# Sensor_tile.net
KiCad netlist of a schematic drawn in EAGLE
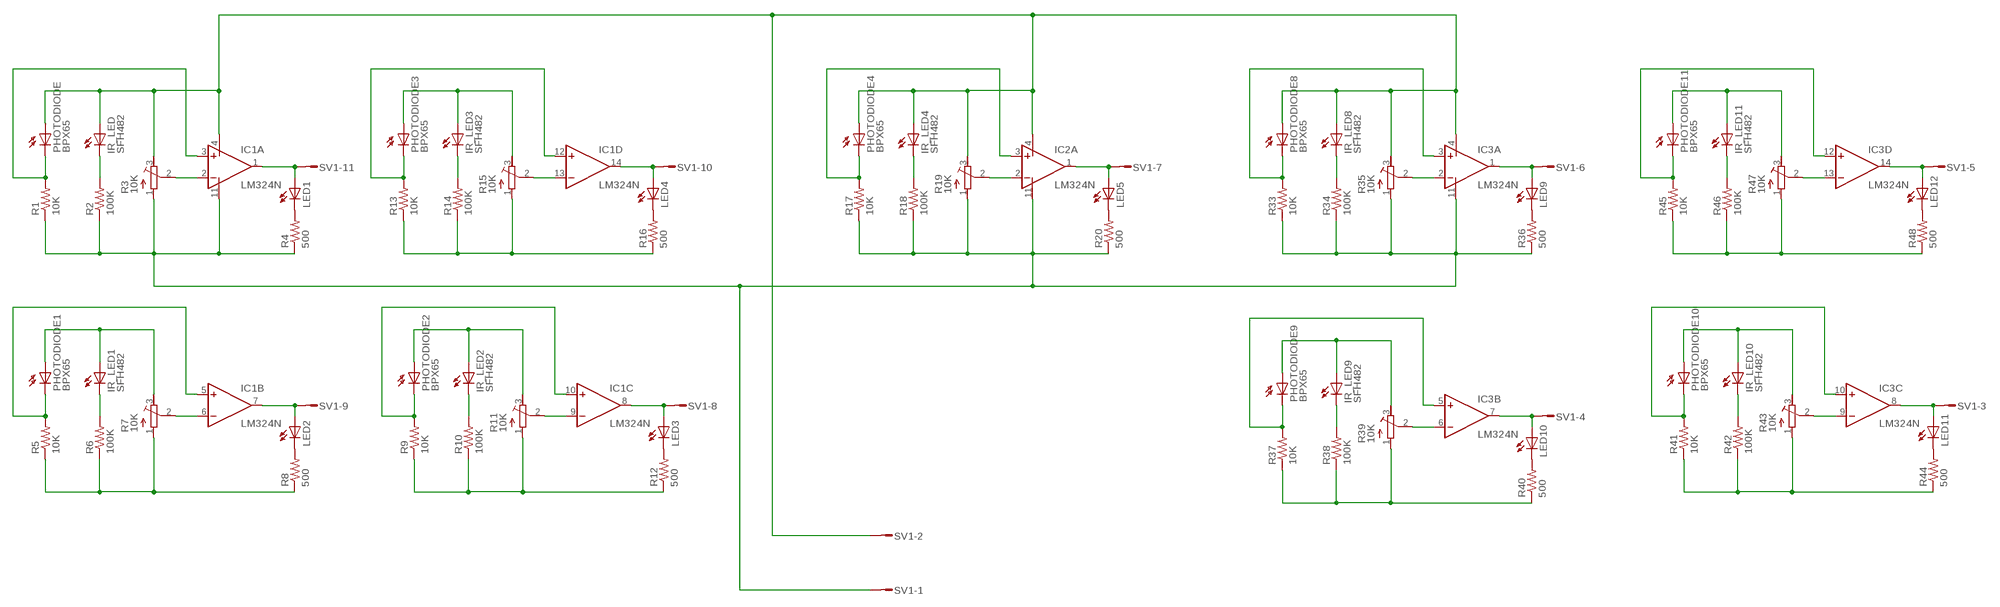
[diagram p0: schematic, sheet 1]

(export (version "E")
  (design (tool "Eeschema 10.0.6"))
  (components
    (comp (ref "IC1")
      (value "LM324N")
      (footprint "eagle-import:DIL14")
      (libsource (lib "eagle-import") (part "LM324N"))
    )
    (comp (ref "IC2")
      (value "LM324N")
      (footprint "eagle-import:DIL14")
      (libsource (lib "eagle-import") (part "LM324N"))
    )
    (comp (ref "IC3")
      (value "LM324N")
      (footprint "eagle-import:DIL14")
      (libsource (lib "eagle-import") (part "LM324N"))
    )
    (comp (ref "IR_LED")
      (value "SFH482")
      (footprint "eagle-import:SFH482")
      (libsource (lib "eagle-import") (part "SFH482"))
    )
    (comp (ref "IR_LED1")
      (value "SFH482")
      (footprint "eagle-import:SFH482")
      (libsource (lib "eagle-import") (part "SFH482"))
    )
    (comp (ref "IR_LED2")
      (value "SFH482")
      (footprint "eagle-import:SFH482")
      (libsource (lib "eagle-import") (part "SFH482"))
    )
    (comp (ref "IR_LED3")
      (value "SFH482")
      (footprint "eagle-import:SFH482")
      (libsource (lib "eagle-import") (part "SFH482"))
    )
    (comp (ref "IR_LED4")
      (value "SFH482")
      (footprint "eagle-import:SFH482")
      (libsource (lib "eagle-import") (part "SFH482"))
    )
    (comp (ref "IR_LED8")
      (value "SFH482")
      (footprint "eagle-import:SFH482")
      (libsource (lib "eagle-import") (part "SFH482"))
    )
    (comp (ref "IR_LED9")
      (value "SFH482")
      (footprint "eagle-import:SFH482")
      (libsource (lib "eagle-import") (part "SFH482"))
    )
    (comp (ref "IR_LED10")
      (value "SFH482")
      (footprint "eagle-import:SFH482")
      (libsource (lib "eagle-import") (part "SFH482"))
    )
    (comp (ref "IR_LED11")
      (value "SFH482")
      (footprint "eagle-import:SFH482")
      (libsource (lib "eagle-import") (part "SFH482"))
    )
    (comp (ref "LED1")
      (value "LED5MM")
      (footprint "eagle-import:LED5MM")
      (libsource (lib "eagle-import") (part "LED5MM"))
    )
    (comp (ref "LED2")
      (value "LED5MM")
      (footprint "eagle-import:LED5MM")
      (libsource (lib "eagle-import") (part "LED5MM"))
    )
    (comp (ref "LED3")
      (value "LED5MM")
      (footprint "eagle-import:LED5MM")
      (libsource (lib "eagle-import") (part "LED5MM"))
    )
    (comp (ref "LED4")
      (value "LED5MM")
      (footprint "eagle-import:LED5MM")
      (libsource (lib "eagle-import") (part "LED5MM"))
    )
    (comp (ref "LED5")
      (value "LED5MM")
      (footprint "eagle-import:LED5MM")
      (libsource (lib "eagle-import") (part "LED5MM"))
    )
    (comp (ref "LED9")
      (value "LED5MM")
      (footprint "eagle-import:LED5MM")
      (libsource (lib "eagle-import") (part "LED5MM"))
    )
    (comp (ref "LED10")
      (value "LED5MM")
      (footprint "eagle-import:LED5MM")
      (libsource (lib "eagle-import") (part "LED5MM"))
    )
    (comp (ref "LED11")
      (value "LED5MM")
      (footprint "eagle-import:LED5MM")
      (libsource (lib "eagle-import") (part "LED5MM"))
    )
    (comp (ref "LED12")
      (value "LED5MM")
      (footprint "eagle-import:LED5MM")
      (libsource (lib "eagle-import") (part "LED5MM"))
    )
    (comp (ref "PHOTODIODE")
      (value "BPX65")
      (footprint "eagle-import:BPX65")
      (fields (field (name "MPN") "BPX65."))
      (libsource (lib "eagle-import") (part "BPX65"))
    )
    (comp (ref "PHOTODIODE1")
      (value "BPX65")
      (footprint "eagle-import:BPX65")
      (fields (field (name "MPN") "BPX65."))
      (libsource (lib "eagle-import") (part "BPX65"))
    )
    (comp (ref "PHOTODIODE2")
      (value "BPX65")
      (footprint "eagle-import:BPX65")
      (fields (field (name "MPN") "BPX65."))
      (libsource (lib "eagle-import") (part "BPX65"))
    )
    (comp (ref "PHOTODIODE3")
      (value "BPX65")
      (footprint "eagle-import:BPX65")
      (fields (field (name "MPN") "BPX65."))
      (libsource (lib "eagle-import") (part "BPX65"))
    )
    (comp (ref "PHOTODIODE4")
      (value "BPX65")
      (footprint "eagle-import:BPX65")
      (fields (field (name "MPN") "BPX65."))
      (libsource (lib "eagle-import") (part "BPX65"))
    )
    (comp (ref "PHOTODIODE8")
      (value "BPX65")
      (footprint "eagle-import:BPX65")
      (fields (field (name "MPN") "BPX65."))
      (libsource (lib "eagle-import") (part "BPX65"))
    )
    (comp (ref "PHOTODIODE9")
      (value "BPX65")
      (footprint "eagle-import:BPX65")
      (fields (field (name "MPN") "BPX65."))
      (libsource (lib "eagle-import") (part "BPX65"))
    )
    (comp (ref "PHOTODIODE10")
      (value "BPX65")
      (footprint "eagle-import:BPX65")
      (fields (field (name "MPN") "BPX65."))
      (libsource (lib "eagle-import") (part "BPX65"))
    )
    (comp (ref "PHOTODIODE11")
      (value "BPX65")
      (footprint "eagle-import:BPX65")
      (fields (field (name "MPN") "BPX65."))
      (libsource (lib "eagle-import") (part "BPX65"))
    )
    (comp (ref "R1")
      (value "10K")
      (footprint "eagle-import:0204_7")
      (libsource (lib "eagle-import") (part "R-US_0204/7"))
    )
    (comp (ref "R2")
      (value "100K")
      (footprint "eagle-import:0204_7")
      (libsource (lib "eagle-import") (part "R-US_0204/7"))
    )
    (comp (ref "R3")
      (value "10K")
      (footprint "eagle-import:RTRIM4G_J")
      (libsource (lib "eagle-import") (part "R-TRIMM4G/J"))
    )
    (comp (ref "R4")
      (value "500")
      (footprint "eagle-import:0204_7")
      (libsource (lib "eagle-import") (part "R-US_0204/7"))
    )
    (comp (ref "R5")
      (value "10K")
      (footprint "eagle-import:0204_7")
      (libsource (lib "eagle-import") (part "R-US_0204/7"))
    )
    (comp (ref "R6")
      (value "100K")
      (footprint "eagle-import:0204_7")
      (libsource (lib "eagle-import") (part "R-US_0204/7"))
    )
    (comp (ref "R7")
      (value "10K")
      (footprint "eagle-import:RTRIM4G_J")
      (libsource (lib "eagle-import") (part "R-TRIMM4G/J"))
    )
    (comp (ref "R8")
      (value "500")
      (footprint "eagle-import:0204_7")
      (libsource (lib "eagle-import") (part "R-US_0204/7"))
    )
    (comp (ref "R9")
      (value "10K")
      (footprint "eagle-import:0204_7")
      (libsource (lib "eagle-import") (part "R-US_0204/7"))
    )
    (comp (ref "R10")
      (value "100K")
      (footprint "eagle-import:0204_7")
      (libsource (lib "eagle-import") (part "R-US_0204/7"))
    )
    (comp (ref "R11")
      (value "10K")
      (footprint "eagle-import:RTRIM4G_J")
      (libsource (lib "eagle-import") (part "R-TRIMM4G/J"))
    )
    (comp (ref "R12")
      (value "500")
      (footprint "eagle-import:0204_7")
      (libsource (lib "eagle-import") (part "R-US_0204/7"))
    )
    (comp (ref "R13")
      (value "10K")
      (footprint "eagle-import:0204_7")
      (libsource (lib "eagle-import") (part "R-US_0204/7"))
    )
    (comp (ref "R14")
      (value "100K")
      (footprint "eagle-import:0204_7")
      (libsource (lib "eagle-import") (part "R-US_0204/7"))
    )
    (comp (ref "R15")
      (value "10K")
      (footprint "eagle-import:RTRIM4G_J")
      (libsource (lib "eagle-import") (part "R-TRIMM4G/J"))
    )
    (comp (ref "R16")
      (value "500")
      (footprint "eagle-import:0204_7")
      (libsource (lib "eagle-import") (part "R-US_0204/7"))
    )
    (comp (ref "R17")
      (value "10K")
      (footprint "eagle-import:0204_7")
      (libsource (lib "eagle-import") (part "R-US_0204/7"))
    )
    (comp (ref "R18")
      (value "100K")
      (footprint "eagle-import:0204_7")
      (libsource (lib "eagle-import") (part "R-US_0204/7"))
    )
    (comp (ref "R19")
      (value "10K")
      (footprint "eagle-import:RTRIM4G_J")
      (libsource (lib "eagle-import") (part "R-TRIMM4G/J"))
    )
    (comp (ref "R20")
      (value "500")
      (footprint "eagle-import:0204_7")
      (libsource (lib "eagle-import") (part "R-US_0204/7"))
    )
    (comp (ref "R33")
      (value "10K")
      (footprint "eagle-import:0204_7")
      (libsource (lib "eagle-import") (part "R-US_0204/7"))
    )
    (comp (ref "R34")
      (value "100K")
      (footprint "eagle-import:0204_7")
      (libsource (lib "eagle-import") (part "R-US_0204/7"))
    )
    (comp (ref "R35")
      (value "10K")
      (footprint "eagle-import:RTRIM4G_J")
      (libsource (lib "eagle-import") (part "R-TRIMM4G/J"))
    )
    (comp (ref "R36")
      (value "500")
      (footprint "eagle-import:0204_7")
      (libsource (lib "eagle-import") (part "R-US_0204/7"))
    )
    (comp (ref "R37")
      (value "10K")
      (footprint "eagle-import:0204_7")
      (libsource (lib "eagle-import") (part "R-US_0204/7"))
    )
    (comp (ref "R38")
      (value "100K")
      (footprint "eagle-import:0204_7")
      (libsource (lib "eagle-import") (part "R-US_0204/7"))
    )
    (comp (ref "R39")
      (value "10K")
      (footprint "eagle-import:RTRIM4G_J")
      (libsource (lib "eagle-import") (part "R-TRIMM4G/J"))
    )
    (comp (ref "R40")
      (value "500")
      (footprint "eagle-import:0204_7")
      (libsource (lib "eagle-import") (part "R-US_0204/7"))
    )
    (comp (ref "R41")
      (value "10K")
      (footprint "eagle-import:0204_7")
      (libsource (lib "eagle-import") (part "R-US_0204/7"))
    )
    (comp (ref "R42")
      (value "100K")
      (footprint "eagle-import:0204_7")
      (libsource (lib "eagle-import") (part "R-US_0204/7"))
    )
    (comp (ref "R43")
      (value "10K")
      (footprint "eagle-import:RTRIM4G_J")
      (libsource (lib "eagle-import") (part "R-TRIMM4G/J"))
    )
    (comp (ref "R44")
      (value "500")
      (footprint "eagle-import:0204_7")
      (libsource (lib "eagle-import") (part "R-US_0204/7"))
    )
    (comp (ref "R45")
      (value "10K")
      (footprint "eagle-import:0204_7")
      (libsource (lib "eagle-import") (part "R-US_0204/7"))
    )
    (comp (ref "R46")
      (value "100K")
      (footprint "eagle-import:0204_7")
      (libsource (lib "eagle-import") (part "R-US_0204/7"))
    )
    (comp (ref "R47")
      (value "10K")
      (footprint "eagle-import:RTRIM4G_J")
      (libsource (lib "eagle-import") (part "R-TRIMM4G/J"))
    )
    (comp (ref "R48")
      (value "500")
      (footprint "eagle-import:0204_7")
      (libsource (lib "eagle-import") (part "R-US_0204/7"))
    )
    (comp (ref "SV1")
      (value "L11P")
      (footprint "eagle-import:L11P")
      (libsource (lib "eagle-import") (part "L11P"))
    )
  )
  (nets
    (net (code "1") (name "Net-(IC1A-+IN)") (class "Default")
      (node (ref "IC1") (pin "3") (pinfunction "+IN_3") (pintype "input"))
      (node (ref "PHOTODIODE") (pin "K") (pinfunction "C_K") (pintype "passive"))
      (node (ref "R1") (pin "2") (pinfunction "2_2") (pintype "passive"))
    )
    (net (code "2") (name "Net-(IC1A--IN)") (class "Default")
      (node (ref "IC1") (pin "2") (pinfunction "-IN_2") (pintype "input"))
      (node (ref "R3") (pin "2") (pinfunction "S_2") (pintype "passive"))
    )
    (net (code "3") (name "Net-(IC1A-OUT)") (class "Default")
      (node (ref "IC1") (pin "1") (pinfunction "OUT_1") (pintype "output"))
      (node (ref "LED1") (pin "A") (pinfunction "A_A") (pintype "passive"))
      (node (ref "SV1") (pin "11") (pinfunction "S_11") (pintype "passive"))
    )
    (net (code "4") (name "Net-(IC1B-+IN)") (class "Default")
      (node (ref "IC1") (pin "5") (pinfunction "+IN_5") (pintype "input"))
      (node (ref "PHOTODIODE1") (pin "K") (pinfunction "C_K") (pintype "passive"))
      (node (ref "R5") (pin "2") (pinfunction "2_2") (pintype "passive"))
    )
    (net (code "5") (name "Net-(IC1B--IN)") (class "Default")
      (node (ref "IC1") (pin "6") (pinfunction "-IN_6") (pintype "input"))
      (node (ref "R7") (pin "2") (pinfunction "S_2") (pintype "passive"))
    )
    (net (code "6") (name "Net-(IC1B-OUT)") (class "Default")
      (node (ref "IC1") (pin "7") (pinfunction "OUT_7") (pintype "output"))
      (node (ref "LED2") (pin "A") (pinfunction "A_A") (pintype "passive"))
      (node (ref "SV1") (pin "9") (pinfunction "S_9") (pintype "passive"))
    )
    (net (code "7") (name "Net-(IC1C-+IN)") (class "Default")
      (node (ref "IC1") (pin "10") (pinfunction "+IN_10") (pintype "input"))
      (node (ref "PHOTODIODE2") (pin "K") (pinfunction "C_K") (pintype "passive"))
      (node (ref "R9") (pin "2") (pinfunction "2_2") (pintype "passive"))
    )
    (net (code "8") (name "Net-(IC1C--IN)") (class "Default")
      (node (ref "IC1") (pin "9") (pinfunction "-IN_9") (pintype "input"))
      (node (ref "R11") (pin "2") (pinfunction "S_2") (pintype "passive"))
    )
    (net (code "9") (name "Net-(IC1C-OUT)") (class "Default")
      (node (ref "IC1") (pin "8") (pinfunction "OUT_8") (pintype "output"))
      (node (ref "LED3") (pin "A") (pinfunction "A_A") (pintype "passive"))
      (node (ref "SV1") (pin "8") (pinfunction "S_8") (pintype "passive"))
    )
    (net (code "10") (name "Net-(IC1D-+IN)") (class "Default")
      (node (ref "IC1") (pin "12") (pinfunction "+IN_12") (pintype "input"))
      (node (ref "PHOTODIODE3") (pin "K") (pinfunction "C_K") (pintype "passive"))
      (node (ref "R13") (pin "2") (pinfunction "2_2") (pintype "passive"))
    )
    (net (code "11") (name "Net-(IC1D--IN)") (class "Default")
      (node (ref "IC1") (pin "13") (pinfunction "-IN_13") (pintype "input"))
      (node (ref "R15") (pin "2") (pinfunction "S_2") (pintype "passive"))
    )
    (net (code "12") (name "Net-(IC1D-OUT)") (class "Default")
      (node (ref "IC1") (pin "14") (pinfunction "OUT_14") (pintype "output"))
      (node (ref "LED4") (pin "A") (pinfunction "A_A") (pintype "passive"))
      (node (ref "SV1") (pin "10") (pinfunction "S_10") (pintype "passive"))
    )
    (net (code "13") (name "Net-(IC1E-V+)") (class "Default")
      (node (ref "IC1") (pin "4") (pinfunction "V+_4") (pintype "power_in"))
      (node (ref "IC2") (pin "4") (pinfunction "V+_4") (pintype "power_in"))
      (node (ref "IC3") (pin "4") (pinfunction "V+_4") (pintype "power_in"))
      (node (ref "IR_LED") (pin "A") (pinfunction "A_A") (pintype "passive"))
      (node (ref "IR_LED4") (pin "A") (pinfunction "A_A") (pintype "passive"))
      (node (ref "IR_LED8") (pin "A") (pinfunction "A_A") (pintype "passive"))
      (node (ref "PHOTODIODE") (pin "A") (pinfunction "A_A") (pintype "passive"))
      (node (ref "PHOTODIODE4") (pin "A") (pinfunction "A_A") (pintype "passive"))
      (node (ref "PHOTODIODE8") (pin "A") (pinfunction "A_A") (pintype "passive"))
      (node (ref "R19") (pin "3") (pinfunction "E_3") (pintype "passive"))
      (node (ref "R3") (pin "3") (pinfunction "E_3") (pintype "passive"))
      (node (ref "R35") (pin "3") (pinfunction "E_3") (pintype "passive"))
      (node (ref "SV1") (pin "2") (pinfunction "S_2") (pintype "passive"))
    )
    (net (code "14") (name "Net-(IC1E-V-)") (class "Default")
      (node (ref "IC1") (pin "11") (pinfunction "V-_11") (pintype "power_in"))
      (node (ref "IC2") (pin "11") (pinfunction "V-_11") (pintype "power_in"))
      (node (ref "IC3") (pin "11") (pinfunction "V-_11") (pintype "power_in"))
      (node (ref "R1") (pin "1") (pinfunction "1_1") (pintype "passive"))
      (node (ref "R17") (pin "1") (pinfunction "1_1") (pintype "passive"))
      (node (ref "R18") (pin "1") (pinfunction "1_1") (pintype "passive"))
      (node (ref "R19") (pin "1") (pinfunction "A_1") (pintype "passive"))
      (node (ref "R2") (pin "1") (pinfunction "1_1") (pintype "passive"))
      (node (ref "R20") (pin "1") (pinfunction "1_1") (pintype "passive"))
      (node (ref "R3") (pin "1") (pinfunction "A_1") (pintype "passive"))
      (node (ref "R33") (pin "1") (pinfunction "1_1") (pintype "passive"))
      (node (ref "R34") (pin "1") (pinfunction "1_1") (pintype "passive"))
      (node (ref "R35") (pin "1") (pinfunction "A_1") (pintype "passive"))
      (node (ref "R36") (pin "1") (pinfunction "1_1") (pintype "passive"))
      (node (ref "R4") (pin "1") (pinfunction "1_1") (pintype "passive"))
      (node (ref "SV1") (pin "1") (pinfunction "S_1") (pintype "passive"))
    )
    (net (code "15") (name "Net-(IC2A-+IN)") (class "Default")
      (node (ref "IC2") (pin "3") (pinfunction "+IN_3") (pintype "input"))
      (node (ref "PHOTODIODE4") (pin "K") (pinfunction "C_K") (pintype "passive"))
      (node (ref "R17") (pin "2") (pinfunction "2_2") (pintype "passive"))
    )
    (net (code "16") (name "Net-(IC2A--IN)") (class "Default")
      (node (ref "IC2") (pin "2") (pinfunction "-IN_2") (pintype "input"))
      (node (ref "R19") (pin "2") (pinfunction "S_2") (pintype "passive"))
    )
    (net (code "17") (name "Net-(IC2A-OUT)") (class "Default")
      (node (ref "IC2") (pin "1") (pinfunction "OUT_1") (pintype "output"))
      (node (ref "LED5") (pin "A") (pinfunction "A_A") (pintype "passive"))
      (node (ref "SV1") (pin "7") (pinfunction "S_7") (pintype "passive"))
    )
    (net (code "18") (name "Net-(IC3A-+IN)") (class "Default")
      (node (ref "IC3") (pin "3") (pinfunction "+IN_3") (pintype "input"))
      (node (ref "PHOTODIODE8") (pin "K") (pinfunction "C_K") (pintype "passive"))
      (node (ref "R33") (pin "2") (pinfunction "2_2") (pintype "passive"))
    )
    (net (code "19") (name "Net-(IC3A--IN)") (class "Default")
      (node (ref "IC3") (pin "2") (pinfunction "-IN_2") (pintype "input"))
      (node (ref "R35") (pin "2") (pinfunction "S_2") (pintype "passive"))
    )
    (net (code "20") (name "Net-(IC3A-OUT)") (class "Default")
      (node (ref "IC3") (pin "1") (pinfunction "OUT_1") (pintype "output"))
      (node (ref "LED9") (pin "A") (pinfunction "A_A") (pintype "passive"))
      (node (ref "SV1") (pin "6") (pinfunction "S_6") (pintype "passive"))
    )
    (net (code "21") (name "Net-(IC3B-+IN)") (class "Default")
      (node (ref "IC3") (pin "5") (pinfunction "+IN_5") (pintype "input"))
      (node (ref "PHOTODIODE9") (pin "K") (pinfunction "C_K") (pintype "passive"))
      (node (ref "R37") (pin "2") (pinfunction "2_2") (pintype "passive"))
    )
    (net (code "22") (name "Net-(IC3B--IN)") (class "Default")
      (node (ref "IC3") (pin "6") (pinfunction "-IN_6") (pintype "input"))
      (node (ref "R39") (pin "2") (pinfunction "S_2") (pintype "passive"))
    )
    (net (code "23") (name "Net-(IC3B-OUT)") (class "Default")
      (node (ref "IC3") (pin "7") (pinfunction "OUT_7") (pintype "output"))
      (node (ref "LED10") (pin "A") (pinfunction "A_A") (pintype "passive"))
      (node (ref "SV1") (pin "4") (pinfunction "S_4") (pintype "passive"))
    )
    (net (code "24") (name "Net-(IC3C-+IN)") (class "Default")
      (node (ref "IC3") (pin "10") (pinfunction "+IN_10") (pintype "input"))
      (node (ref "PHOTODIODE10") (pin "K") (pinfunction "C_K") (pintype "passive"))
      (node (ref "R41") (pin "2") (pinfunction "2_2") (pintype "passive"))
    )
    (net (code "25") (name "Net-(IC3C--IN)") (class "Default")
      (node (ref "IC3") (pin "9") (pinfunction "-IN_9") (pintype "input"))
      (node (ref "R43") (pin "2") (pinfunction "S_2") (pintype "passive"))
    )
    (net (code "26") (name "Net-(IC3C-OUT)") (class "Default")
      (node (ref "IC3") (pin "8") (pinfunction "OUT_8") (pintype "output"))
      (node (ref "LED11") (pin "A") (pinfunction "A_A") (pintype "passive"))
      (node (ref "SV1") (pin "3") (pinfunction "S_3") (pintype "passive"))
    )
    (net (code "27") (name "Net-(IC3D-+IN)") (class "Default")
      (node (ref "IC3") (pin "12") (pinfunction "+IN_12") (pintype "input"))
      (node (ref "PHOTODIODE11") (pin "K") (pinfunction "C_K") (pintype "passive"))
      (node (ref "R45") (pin "2") (pinfunction "2_2") (pintype "passive"))
    )
    (net (code "28") (name "Net-(IC3D--IN)") (class "Default")
      (node (ref "IC3") (pin "13") (pinfunction "-IN_13") (pintype "input"))
      (node (ref "R47") (pin "2") (pinfunction "S_2") (pintype "passive"))
    )
    (net (code "29") (name "Net-(IC3D-OUT)") (class "Default")
      (node (ref "IC3") (pin "14") (pinfunction "OUT_14") (pintype "output"))
      (node (ref "LED12") (pin "A") (pinfunction "A_A") (pintype "passive"))
      (node (ref "SV1") (pin "5") (pinfunction "S_5") (pintype "passive"))
    )
    (net (code "30") (name "Net-(IR_LED-C)") (class "Default")
      (node (ref "IR_LED") (pin "K") (pinfunction "C_K") (pintype "passive"))
      (node (ref "R2") (pin "2") (pinfunction "2_2") (pintype "passive"))
    )
    (net (code "31") (name "Net-(IR_LED1-C)") (class "Default")
      (node (ref "IR_LED1") (pin "K") (pinfunction "C_K") (pintype "passive"))
      (node (ref "R6") (pin "2") (pinfunction "2_2") (pintype "passive"))
    )
    (net (code "32") (name "Net-(IR_LED2-C)") (class "Default")
      (node (ref "IR_LED2") (pin "K") (pinfunction "C_K") (pintype "passive"))
      (node (ref "R10") (pin "2") (pinfunction "2_2") (pintype "passive"))
    )
    (net (code "33") (name "Net-(IR_LED3-C)") (class "Default")
      (node (ref "IR_LED3") (pin "K") (pinfunction "C_K") (pintype "passive"))
      (node (ref "R14") (pin "2") (pinfunction "2_2") (pintype "passive"))
    )
    (net (code "34") (name "Net-(IR_LED4-C)") (class "Default")
      (node (ref "IR_LED4") (pin "K") (pinfunction "C_K") (pintype "passive"))
      (node (ref "R18") (pin "2") (pinfunction "2_2") (pintype "passive"))
    )
    (net (code "35") (name "Net-(IR_LED8-C)") (class "Default")
      (node (ref "IR_LED8") (pin "K") (pinfunction "C_K") (pintype "passive"))
      (node (ref "R34") (pin "2") (pinfunction "2_2") (pintype "passive"))
    )
    (net (code "36") (name "Net-(IR_LED9-C)") (class "Default")
      (node (ref "IR_LED9") (pin "K") (pinfunction "C_K") (pintype "passive"))
      (node (ref "R38") (pin "2") (pinfunction "2_2") (pintype "passive"))
    )
    (net (code "37") (name "Net-(IR_LED10-C)") (class "Default")
      (node (ref "IR_LED10") (pin "K") (pinfunction "C_K") (pintype "passive"))
      (node (ref "R42") (pin "2") (pinfunction "2_2") (pintype "passive"))
    )
    (net (code "38") (name "Net-(IR_LED11-C)") (class "Default")
      (node (ref "IR_LED11") (pin "K") (pinfunction "C_K") (pintype "passive"))
      (node (ref "R46") (pin "2") (pinfunction "2_2") (pintype "passive"))
    )
    (net (code "39") (name "Net-(LED1-C)") (class "Default")
      (node (ref "LED1") (pin "K") (pinfunction "C_K") (pintype "passive"))
      (node (ref "R4") (pin "2") (pinfunction "2_2") (pintype "passive"))
    )
    (net (code "40") (name "Net-(LED2-C)") (class "Default")
      (node (ref "LED2") (pin "K") (pinfunction "C_K") (pintype "passive"))
      (node (ref "R8") (pin "2") (pinfunction "2_2") (pintype "passive"))
    )
    (net (code "41") (name "Net-(LED3-C)") (class "Default")
      (node (ref "LED3") (pin "K") (pinfunction "C_K") (pintype "passive"))
      (node (ref "R12") (pin "2") (pinfunction "2_2") (pintype "passive"))
    )
    (net (code "42") (name "Net-(LED4-C)") (class "Default")
      (node (ref "LED4") (pin "K") (pinfunction "C_K") (pintype "passive"))
      (node (ref "R16") (pin "2") (pinfunction "2_2") (pintype "passive"))
    )
    (net (code "43") (name "Net-(LED5-C)") (class "Default")
      (node (ref "LED5") (pin "K") (pinfunction "C_K") (pintype "passive"))
      (node (ref "R20") (pin "2") (pinfunction "2_2") (pintype "passive"))
    )
    (net (code "44") (name "Net-(LED9-C)") (class "Default")
      (node (ref "LED9") (pin "K") (pinfunction "C_K") (pintype "passive"))
      (node (ref "R36") (pin "2") (pinfunction "2_2") (pintype "passive"))
    )
    (net (code "45") (name "Net-(LED10-C)") (class "Default")
      (node (ref "LED10") (pin "K") (pinfunction "C_K") (pintype "passive"))
      (node (ref "R40") (pin "2") (pinfunction "2_2") (pintype "passive"))
    )
    (net (code "46") (name "Net-(LED11-C)") (class "Default")
      (node (ref "LED11") (pin "K") (pinfunction "C_K") (pintype "passive"))
      (node (ref "R44") (pin "2") (pinfunction "2_2") (pintype "passive"))
    )
    (net (code "47") (name "Net-(LED12-C)") (class "Default")
      (node (ref "LED12") (pin "K") (pinfunction "C_K") (pintype "passive"))
      (node (ref "R48") (pin "2") (pinfunction "2_2") (pintype "passive"))
    )
    (net (code "48") (name "Net-(R7-A)") (class "Default")
      (node (ref "R5") (pin "1") (pinfunction "1_1") (pintype "passive"))
      (node (ref "R6") (pin "1") (pinfunction "1_1") (pintype "passive"))
      (node (ref "R7") (pin "1") (pinfunction "A_1") (pintype "passive"))
      (node (ref "R8") (pin "1") (pinfunction "1_1") (pintype "passive"))
    )
    (net (code "49") (name "Net-(R7-E)") (class "Default")
      (node (ref "IR_LED1") (pin "A") (pinfunction "A_A") (pintype "passive"))
      (node (ref "PHOTODIODE1") (pin "A") (pinfunction "A_A") (pintype "passive"))
      (node (ref "R7") (pin "3") (pinfunction "E_3") (pintype "passive"))
    )
    (net (code "50") (name "Net-(R11-A)") (class "Default")
      (node (ref "R10") (pin "1") (pinfunction "1_1") (pintype "passive"))
      (node (ref "R11") (pin "1") (pinfunction "A_1") (pintype "passive"))
      (node (ref "R12") (pin "1") (pinfunction "1_1") (pintype "passive"))
      (node (ref "R9") (pin "1") (pinfunction "1_1") (pintype "passive"))
    )
    (net (code "51") (name "Net-(R11-E)") (class "Default")
      (node (ref "IR_LED2") (pin "A") (pinfunction "A_A") (pintype "passive"))
      (node (ref "PHOTODIODE2") (pin "A") (pinfunction "A_A") (pintype "passive"))
      (node (ref "R11") (pin "3") (pinfunction "E_3") (pintype "passive"))
    )
    (net (code "52") (name "Net-(R15-A)") (class "Default")
      (node (ref "R13") (pin "1") (pinfunction "1_1") (pintype "passive"))
      (node (ref "R14") (pin "1") (pinfunction "1_1") (pintype "passive"))
      (node (ref "R15") (pin "1") (pinfunction "A_1") (pintype "passive"))
      (node (ref "R16") (pin "1") (pinfunction "1_1") (pintype "passive"))
    )
    (net (code "53") (name "Net-(R15-E)") (class "Default")
      (node (ref "IR_LED3") (pin "A") (pinfunction "A_A") (pintype "passive"))
      (node (ref "PHOTODIODE3") (pin "A") (pinfunction "A_A") (pintype "passive"))
      (node (ref "R15") (pin "3") (pinfunction "E_3") (pintype "passive"))
    )
    (net (code "54") (name "Net-(R39-A)") (class "Default")
      (node (ref "R37") (pin "1") (pinfunction "1_1") (pintype "passive"))
      (node (ref "R38") (pin "1") (pinfunction "1_1") (pintype "passive"))
      (node (ref "R39") (pin "1") (pinfunction "A_1") (pintype "passive"))
      (node (ref "R40") (pin "1") (pinfunction "1_1") (pintype "passive"))
    )
    (net (code "55") (name "Net-(R39-E)") (class "Default")
      (node (ref "IR_LED9") (pin "A") (pinfunction "A_A") (pintype "passive"))
      (node (ref "PHOTODIODE9") (pin "A") (pinfunction "A_A") (pintype "passive"))
      (node (ref "R39") (pin "3") (pinfunction "E_3") (pintype "passive"))
    )
    (net (code "56") (name "Net-(R43-A)") (class "Default")
      (node (ref "R41") (pin "1") (pinfunction "1_1") (pintype "passive"))
      (node (ref "R42") (pin "1") (pinfunction "1_1") (pintype "passive"))
      (node (ref "R43") (pin "1") (pinfunction "A_1") (pintype "passive"))
      (node (ref "R44") (pin "1") (pinfunction "1_1") (pintype "passive"))
    )
    (net (code "57") (name "Net-(R43-E)") (class "Default")
      (node (ref "IR_LED10") (pin "A") (pinfunction "A_A") (pintype "passive"))
      (node (ref "PHOTODIODE10") (pin "A") (pinfunction "A_A") (pintype "passive"))
      (node (ref "R43") (pin "3") (pinfunction "E_3") (pintype "passive"))
    )
    (net (code "58") (name "Net-(R47-A)") (class "Default")
      (node (ref "R45") (pin "1") (pinfunction "1_1") (pintype "passive"))
      (node (ref "R46") (pin "1") (pinfunction "1_1") (pintype "passive"))
      (node (ref "R47") (pin "1") (pinfunction "A_1") (pintype "passive"))
      (node (ref "R48") (pin "1") (pinfunction "1_1") (pintype "passive"))
    )
    (net (code "59") (name "Net-(R47-E)") (class "Default")
      (node (ref "IR_LED11") (pin "A") (pinfunction "A_A") (pintype "passive"))
      (node (ref "PHOTODIODE11") (pin "A") (pinfunction "A_A") (pintype "passive"))
      (node (ref "R47") (pin "3") (pinfunction "E_3") (pintype "passive"))
    )
  )
)
